# pic5.net
KiCad netlist of a schematic drawn in EAGLE
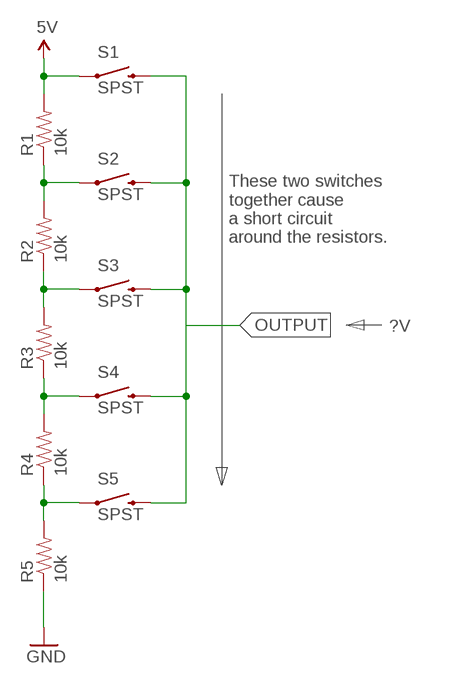
[diagram p0: schematic, sheet 1]

(export (version "E")
  (design (tool "Eeschema 10.0.6"))
  (components
    (comp (ref "R1")
      (value "10k")
      (footprint "eagle-import:0603-RES")
      (fields (field (name "PROD_ID") "RES-00818"))
      (libsource (lib "eagle-import") (part "330OHM1/10W1%(0603)"))
    )
    (comp (ref "R2")
      (value "10k")
      (footprint "eagle-import:0603-RES")
      (fields (field (name "PROD_ID") "RES-00818"))
      (libsource (lib "eagle-import") (part "330OHM1/10W1%(0603)"))
    )
    (comp (ref "R3")
      (value "10k")
      (footprint "eagle-import:0603-RES")
      (fields (field (name "PROD_ID") "RES-00818"))
      (libsource (lib "eagle-import") (part "330OHM1/10W1%(0603)"))
    )
    (comp (ref "R4")
      (value "10k")
      (footprint "eagle-import:0603-RES")
      (fields (field (name "PROD_ID") "RES-00818"))
      (libsource (lib "eagle-import") (part "330OHM1/10W1%(0603)"))
    )
    (comp (ref "R5")
      (value "10k")
      (footprint "eagle-import:0603-RES")
      (fields (field (name "PROD_ID") "RES-00818"))
      (libsource (lib "eagle-import") (part "330OHM1/10W1%(0603)"))
    )
    (comp (ref "S1")
      (value "SPST")
      (footprint "eagle-import:TACTILE-PTH-12MM")
      (libsource (lib "eagle-import") (part "SWITCH-MOMENTARY-212MM"))
    )
    (comp (ref "S2")
      (value "SPST")
      (footprint "eagle-import:TACTILE-PTH-12MM")
      (libsource (lib "eagle-import") (part "SWITCH-MOMENTARY-212MM"))
    )
    (comp (ref "S3")
      (value "SPST")
      (footprint "eagle-import:TACTILE-PTH-12MM")
      (libsource (lib "eagle-import") (part "SWITCH-MOMENTARY-212MM"))
    )
    (comp (ref "S4")
      (value "SPST")
      (footprint "eagle-import:TACTILE-PTH-12MM")
      (libsource (lib "eagle-import") (part "SWITCH-MOMENTARY-212MM"))
    )
    (comp (ref "S5")
      (value "SPST")
      (footprint "eagle-import:TACTILE-PTH-12MM")
      (libsource (lib "eagle-import") (part "SWITCH-MOMENTARY-212MM"))
    )
  )
  (nets
    (net (code "1") (name "5V") (class "Default")
      (node (ref "R1") (pin "2") (pinfunction "2_2") (pintype "passive"))
      (node (ref "S1") (pin "1") (pinfunction "1_1") (pintype "passive"))
    )
    (net (code "2") (name "GND") (class "Default")
      (node (ref "R5") (pin "1") (pinfunction "1_1") (pintype "passive"))
    )
    (net (code "3") (name "Net-(R1-Pad1)") (class "Default")
      (node (ref "R1") (pin "1") (pinfunction "1_1") (pintype "passive"))
      (node (ref "R2") (pin "2") (pinfunction "2_2") (pintype "passive"))
      (node (ref "S2") (pin "1") (pinfunction "1_1") (pintype "passive"))
    )
    (net (code "4") (name "Net-(R2-Pad1)") (class "Default")
      (node (ref "R2") (pin "1") (pinfunction "1_1") (pintype "passive"))
      (node (ref "R3") (pin "2") (pinfunction "2_2") (pintype "passive"))
      (node (ref "S3") (pin "1") (pinfunction "1_1") (pintype "passive"))
    )
    (net (code "5") (name "Net-(R3-Pad1)") (class "Default")
      (node (ref "R3") (pin "1") (pinfunction "1_1") (pintype "passive"))
      (node (ref "R4") (pin "2") (pinfunction "2_2") (pintype "passive"))
      (node (ref "S4") (pin "1") (pinfunction "1_1") (pintype "passive"))
    )
    (net (code "6") (name "Net-(R4-Pad1)") (class "Default")
      (node (ref "R4") (pin "1") (pinfunction "1_1") (pintype "passive"))
      (node (ref "R5") (pin "2") (pinfunction "2_2") (pintype "passive"))
      (node (ref "S5") (pin "1") (pinfunction "1_1") (pintype "passive"))
    )
    (net (code "7") (name "OUTPUT") (class "Default")
      (node (ref "S1") (pin "3") (pinfunction "2_3") (pintype "passive"))
      (node (ref "S2") (pin "3") (pinfunction "2_3") (pintype "passive"))
      (node (ref "S3") (pin "3") (pinfunction "2_3") (pintype "passive"))
      (node (ref "S4") (pin "3") (pinfunction "2_3") (pintype "passive"))
      (node (ref "S5") (pin "3") (pinfunction "2_3") (pintype "passive"))
    )
  )
)
